# Switch_Module.net
KiCad netlist of a schematic drawn in EAGLE
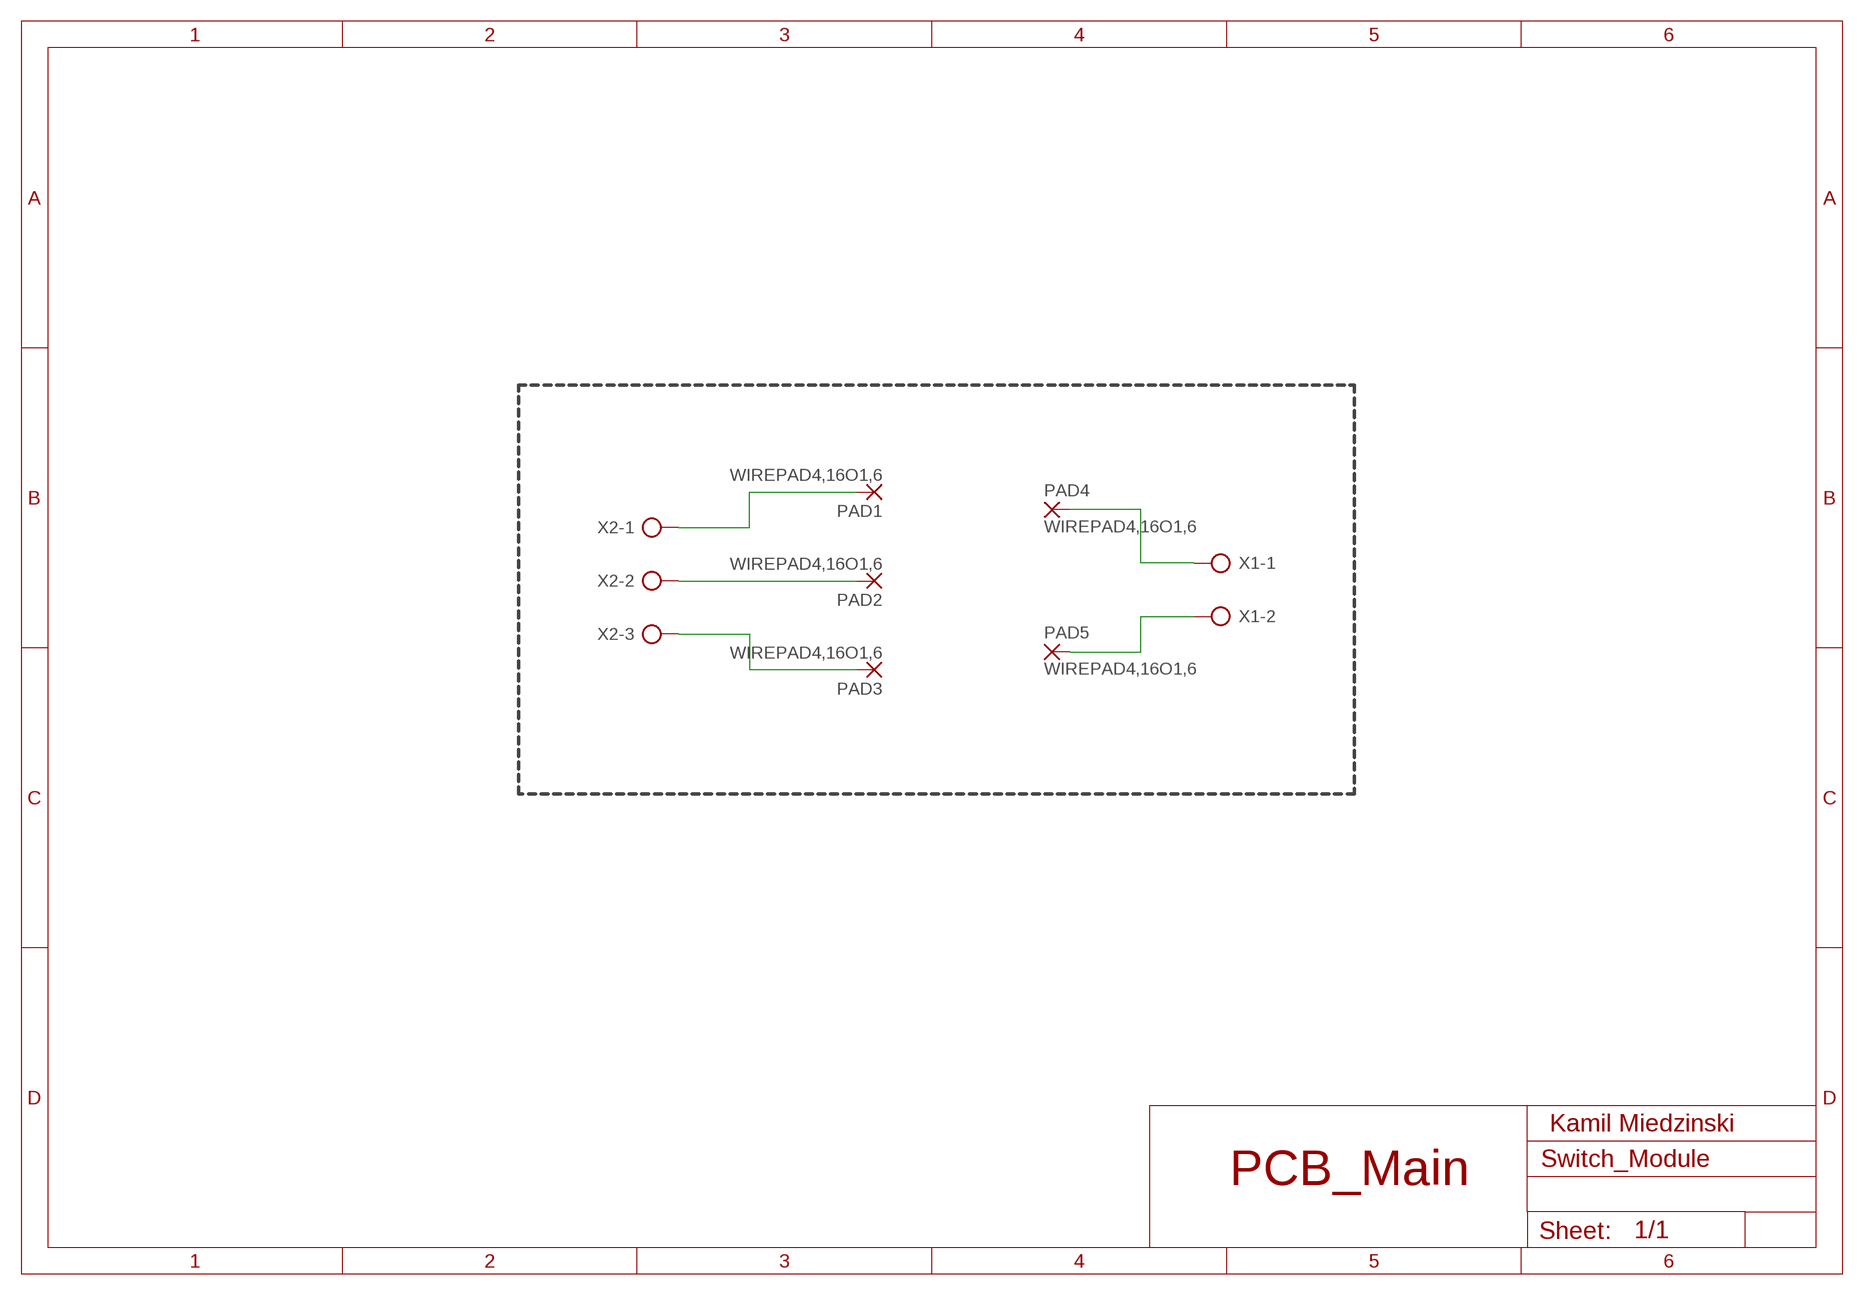
[diagram p0: schematic, sheet 1]

(export (version "E")
  (design (tool "Eeschema 10.0.6"))
  (components
    (comp (ref "PAD1")
      (value "WIREPAD4,16O1,6")
      (footprint "eagle-import:4,16O1,6")
      (libsource (lib "eagle-import") (part "WIREPAD4,16O1,6"))
    )
    (comp (ref "PAD2")
      (value "WIREPAD4,16O1,6")
      (footprint "eagle-import:4,16O1,6")
      (libsource (lib "eagle-import") (part "WIREPAD4,16O1,6"))
    )
    (comp (ref "PAD3")
      (value "WIREPAD4,16O1,6")
      (footprint "eagle-import:4,16O1,6")
      (libsource (lib "eagle-import") (part "WIREPAD4,16O1,6"))
    )
    (comp (ref "PAD4")
      (value "WIREPAD4,16O1,6")
      (footprint "eagle-import:4,16O1,6")
      (libsource (lib "eagle-import") (part "WIREPAD4,16O1,6"))
    )
    (comp (ref "PAD5")
      (value "WIREPAD4,16O1,6")
      (footprint "eagle-import:4,16O1,6")
      (libsource (lib "eagle-import") (part "WIREPAD4,16O1,6"))
    )
    (comp (ref "X1")
      (value "GMKDSP_3/2")
      (footprint "eagle-import:GMKDSP_3_2")
      (libsource (lib "eagle-import") (part "GMKDSP_3/2"))
    )
    (comp (ref "X2")
      (value "MKDS_3/3")
      (footprint "eagle-import:MKDS_3_3")
      (libsource (lib "eagle-import") (part "MKDS_3/3"))
    )
  )
  (nets
    (net (code "1") (name "Net-(PAD1-P)") (class "Default")
      (node (ref "PAD1") (pin "1") (pinfunction "P_1") (pintype "passive"))
      (node (ref "X2") (pin "1") (pinfunction "KL_1") (pintype "passive"))
    )
    (net (code "2") (name "Net-(PAD2-P)") (class "Default")
      (node (ref "PAD2") (pin "1") (pinfunction "P_1") (pintype "passive"))
      (node (ref "X2") (pin "2") (pinfunction "KL_2") (pintype "passive"))
    )
    (net (code "3") (name "Net-(PAD3-P)") (class "Default")
      (node (ref "PAD3") (pin "1") (pinfunction "P_1") (pintype "passive"))
      (node (ref "X2") (pin "3") (pinfunction "KL_3") (pintype "passive"))
    )
    (net (code "4") (name "Net-(PAD4-P)") (class "Default")
      (node (ref "PAD4") (pin "1") (pinfunction "P_1") (pintype "passive"))
      (node (ref "X1") (pin "1") (pinfunction "KL_1") (pintype "passive"))
    )
    (net (code "5") (name "Net-(PAD5-P)") (class "Default")
      (node (ref "PAD5") (pin "1") (pinfunction "P_1") (pintype "passive"))
      (node (ref "X1") (pin "2") (pinfunction "KL_2") (pintype "passive"))
    )
  )
)
